# voicemodulator_schm.net
KiCad netlist of a schematic drawn in EAGLE
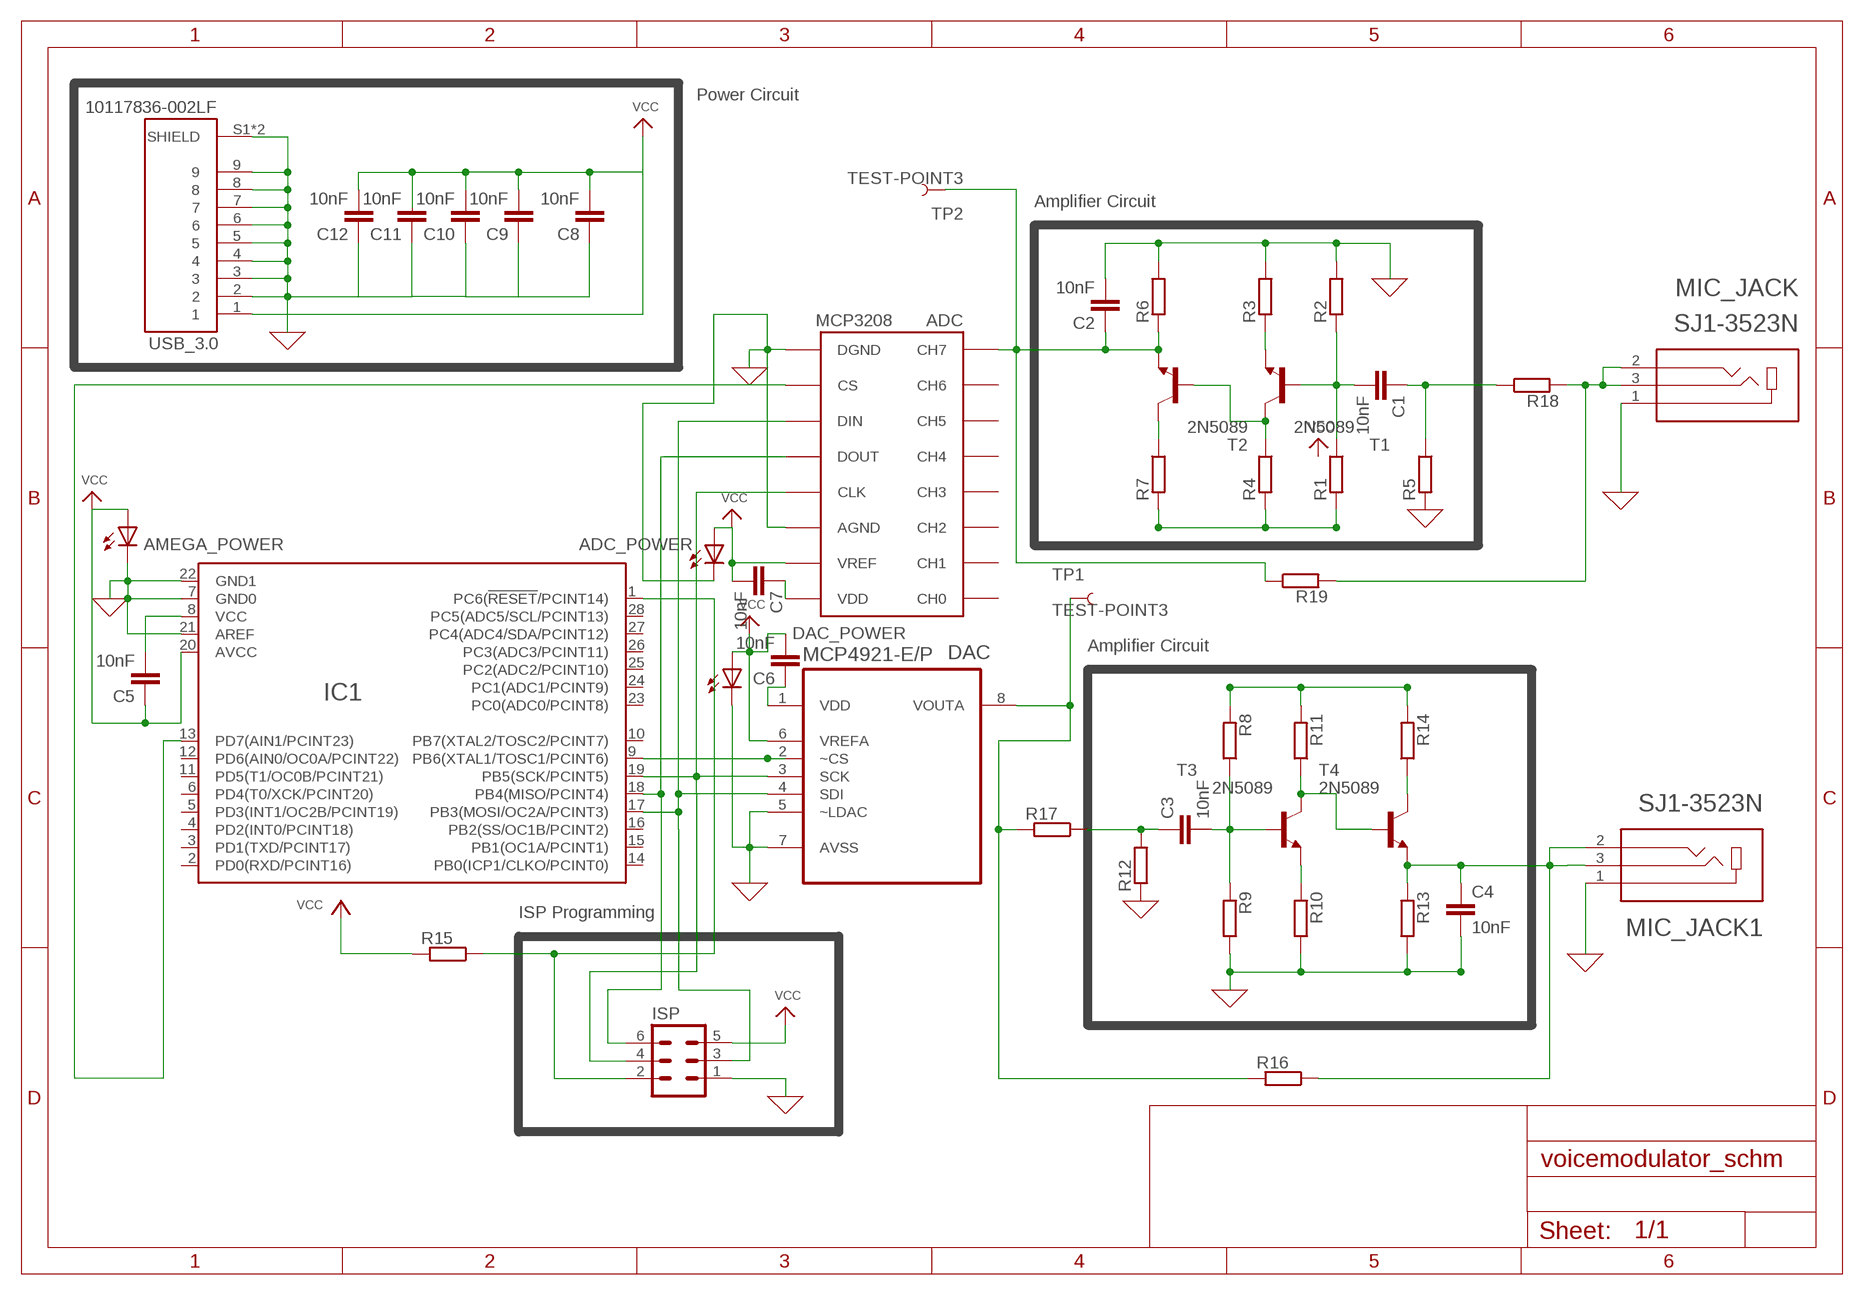
[diagram p0: schematic, sheet 1]

(export (version "E")
  (design (tool "Eeschema 10.0.6"))
  (components
    (comp (ref "ADC")
      (value "MCP3208")
      (footprint "eagle-import:DIL16")
      (libsource (lib "eagle-import") (part "MCP3208"))
    )
    (comp (ref "ADC_POWER")
      (value "LED10MM")
      (footprint "eagle-import:LED10MM")
      (libsource (lib "eagle-import") (part "LED10MM"))
    )
    (comp (ref "AMEGA_POWER")
      (value "LED10MM")
      (footprint "eagle-import:LED10MM")
      (libsource (lib "eagle-import") (part "LED10MM"))
    )
    (comp (ref "C1")
      (value "10nF")
      (footprint "eagle-import:0603")
      (libsource (lib "eagle-import") (part "10NF-0603-50V-10%"))
    )
    (comp (ref "C2")
      (value "10nF")
      (footprint "eagle-import:0603")
      (libsource (lib "eagle-import") (part "10NF-0603-50V-10%"))
    )
    (comp (ref "C3")
      (value "10nF")
      (footprint "eagle-import:0603")
      (libsource (lib "eagle-import") (part "10NF-0603-50V-10%"))
    )
    (comp (ref "C4")
      (value "10nF")
      (footprint "eagle-import:0603")
      (libsource (lib "eagle-import") (part "10NF-0603-50V-10%"))
    )
    (comp (ref "C5")
      (value "10nF")
      (footprint "eagle-import:0603")
      (libsource (lib "eagle-import") (part "10NF-0603-50V-10%"))
    )
    (comp (ref "C6")
      (value "10nF")
      (footprint "eagle-import:0603")
      (libsource (lib "eagle-import") (part "10NF-0603-50V-10%"))
    )
    (comp (ref "C7")
      (value "10nF")
      (footprint "eagle-import:0603")
      (libsource (lib "eagle-import") (part "10NF-0603-50V-10%"))
    )
    (comp (ref "C8")
      (value "10nF")
      (footprint "eagle-import:0603")
      (libsource (lib "eagle-import") (part "10NF-0603-50V-10%"))
    )
    (comp (ref "C9")
      (value "10nF")
      (footprint "eagle-import:0603")
      (libsource (lib "eagle-import") (part "10NF-0603-50V-10%"))
    )
    (comp (ref "C10")
      (value "10nF")
      (footprint "eagle-import:0603")
      (libsource (lib "eagle-import") (part "10NF-0603-50V-10%"))
    )
    (comp (ref "C11")
      (value "10nF")
      (footprint "eagle-import:0603")
      (libsource (lib "eagle-import") (part "10NF-0603-50V-10%"))
    )
    (comp (ref "C12")
      (value "10nF")
      (footprint "eagle-import:0603")
      (libsource (lib "eagle-import") (part "10NF-0603-50V-10%"))
    )
    (comp (ref "DAC")
      (value "MCP4921-E/P")
      (footprint "eagle-import:DIP254P762X432-8")
      (libsource (lib "eagle-import") (part "MCP4921-E/P"))
    )
    (comp (ref "DAC_POWER")
      (value "LED10MM")
      (footprint "eagle-import:LED10MM")
      (libsource (lib "eagle-import") (part "LED10MM"))
    )
    (comp (ref "IC1")
      (value "ATMEGA48/88/168/328-PU(DIP28)PU")
      (footprint "eagle-import:DIL28")
      (libsource (lib "eagle-import") (part "ATMEGA48/88/168/328-PU(DIP28)PU"))
    )
    (comp (ref "ISP")
      (value "MA03-2")
      (footprint "eagle-import:MA03-2")
      (libsource (lib "eagle-import") (part "MA03-2"))
    )
    (comp (ref "MIC_JACK")
      (value "SJ1-3523N")
      (footprint "eagle-import:CUI_SJ1-3523N")
      (fields (field (name "MANUFACTURER") "CUI"))
      (libsource (lib "eagle-import") (part "SJ1-3523N"))
    )
    (comp (ref "MIC_JACK1")
      (value "SJ1-3523N")
      (footprint "eagle-import:CUI_SJ1-3523N")
      (fields (field (name "MANUFACTURER") "CUI"))
      (libsource (lib "eagle-import") (part "SJ1-3523N"))
    )
    (comp (ref "R1")
      (value "SMR-WAV")
      (footprint "eagle-import:SMS-WAV")
      (libsource (lib "eagle-import") (part "SMR-WAV"))
    )
    (comp (ref "R2")
      (value "SMR-WAV")
      (footprint "eagle-import:SMS-WAV")
      (libsource (lib "eagle-import") (part "SMR-WAV"))
    )
    (comp (ref "R3")
      (value "SMR-WAV")
      (footprint "eagle-import:SMS-WAV")
      (libsource (lib "eagle-import") (part "SMR-WAV"))
    )
    (comp (ref "R4")
      (value "SMR-WAV")
      (footprint "eagle-import:SMS-WAV")
      (libsource (lib "eagle-import") (part "SMR-WAV"))
    )
    (comp (ref "R5")
      (value "SMR-WAV")
      (footprint "eagle-import:SMS-WAV")
      (libsource (lib "eagle-import") (part "SMR-WAV"))
    )
    (comp (ref "R6")
      (value "SMR-WAV")
      (footprint "eagle-import:SMS-WAV")
      (libsource (lib "eagle-import") (part "SMR-WAV"))
    )
    (comp (ref "R7")
      (value "SMR-WAV")
      (footprint "eagle-import:SMS-WAV")
      (libsource (lib "eagle-import") (part "SMR-WAV"))
    )
    (comp (ref "R8")
      (value "SMR-WAV")
      (footprint "eagle-import:SMS-WAV")
      (libsource (lib "eagle-import") (part "SMR-WAV"))
    )
    (comp (ref "R9")
      (value "SMR-WAV")
      (footprint "eagle-import:SMS-WAV")
      (libsource (lib "eagle-import") (part "SMR-WAV"))
    )
    (comp (ref "R10")
      (value "SMR-WAV")
      (footprint "eagle-import:SMS-WAV")
      (libsource (lib "eagle-import") (part "SMR-WAV"))
    )
    (comp (ref "R11")
      (value "SMR-WAV")
      (footprint "eagle-import:SMS-WAV")
      (libsource (lib "eagle-import") (part "SMR-WAV"))
    )
    (comp (ref "R12")
      (value "SMR-WAV")
      (footprint "eagle-import:SMS-WAV")
      (libsource (lib "eagle-import") (part "SMR-WAV"))
    )
    (comp (ref "R13")
      (value "SMR-WAV")
      (footprint "eagle-import:SMS-WAV")
      (libsource (lib "eagle-import") (part "SMR-WAV"))
    )
    (comp (ref "R14")
      (value "SMR-WAV")
      (footprint "eagle-import:SMS-WAV")
      (libsource (lib "eagle-import") (part "SMR-WAV"))
    )
    (comp (ref "R15")
      (value "SMR-WAV")
      (footprint "eagle-import:SMS-WAV")
      (libsource (lib "eagle-import") (part "SMR-WAV"))
    )
    (comp (ref "R16")
      (value "SMR-WAV")
      (footprint "eagle-import:SMS-WAV")
      (libsource (lib "eagle-import") (part "SMR-WAV"))
    )
    (comp (ref "R17")
      (value "SMR-WAV")
      (footprint "eagle-import:SMS-WAV")
      (libsource (lib "eagle-import") (part "SMR-WAV"))
    )
    (comp (ref "R18")
      (value "SMR-WAV")
      (footprint "eagle-import:SMS-WAV")
      (libsource (lib "eagle-import") (part "SMR-WAV"))
    )
    (comp (ref "R19")
      (value "SMR-WAV")
      (footprint "eagle-import:SMS-WAV")
      (libsource (lib "eagle-import") (part "SMR-WAV"))
    )
    (comp (ref "T1")
      (value "2N5089")
      (footprint "eagle-import:TO92")
      (libsource (lib "eagle-import") (part "2N5089"))
    )
    (comp (ref "T2")
      (value "2N5089")
      (footprint "eagle-import:TO92")
      (libsource (lib "eagle-import") (part "2N5089"))
    )
    (comp (ref "T3")
      (value "2N5089")
      (footprint "eagle-import:TO92")
      (libsource (lib "eagle-import") (part "2N5089"))
    )
    (comp (ref "T4")
      (value "2N5089")
      (footprint "eagle-import:TO92")
      (libsource (lib "eagle-import") (part "2N5089"))
    )
    (comp (ref "TP1")
      (value "TEST-POINT3")
      (footprint "eagle-import:PAD.03X.03")
      (libsource (lib "eagle-import") (part "TEST-POINT3"))
    )
    (comp (ref "TP2")
      (value "TEST-POINT3")
      (footprint "eagle-import:PAD.03X.03")
      (libsource (lib "eagle-import") (part "TEST-POINT3"))
    )
    (comp (ref "USB_3.0")
      (value "10117836-002LF")
      (footprint "eagle-import:AMPHENOL_10117836-002LF")
      (fields (field (name "MF") "Amphenol FCI"))
      (libsource (lib "eagle-import") (part "10117836-002LF"))
    )
  )
  (nets
    (net (code "1") (name "GND") (class "Default")
      (node (ref "ADC") (pin "AGND") (pinfunction "AGND_AGND") (pintype "power_in"))
      (node (ref "ADC") (pin "DGND") (pinfunction "DGND_DGND") (pintype "power_in"))
      (node (ref "ADC_POWER") (pin "K") (pinfunction "C_K") (pintype "passive"))
      (node (ref "AMEGA_POWER") (pin "K") (pinfunction "C_K") (pintype "passive"))
      (node (ref "C10") (pin "1") (pinfunction "1_1") (pintype "passive"))
      (node (ref "C11") (pin "1") (pinfunction "1_1") (pintype "passive"))
      (node (ref "C12") (pin "1") (pinfunction "1_1") (pintype "passive"))
      (node (ref "C2") (pin "2") (pinfunction "2_2") (pintype "passive"))
      (node (ref "C4") (pin "2") (pinfunction "2_2") (pintype "passive"))
      (node (ref "C8") (pin "1") (pinfunction "1_1") (pintype "passive"))
      (node (ref "C9") (pin "1") (pinfunction "1_1") (pintype "passive"))
      (node (ref "DAC") (pin "5") (pinfunction "~{LDAC}_5") (pintype "input"))
      (node (ref "DAC") (pin "7") (pinfunction "AVSS_7") (pintype "passive"))
      (node (ref "DAC_POWER") (pin "K") (pinfunction "C_K") (pintype "passive"))
      (node (ref "IC1") (pin "21") (pinfunction "AREF_21") (pintype "passive"))
      (node (ref "IC1") (pin "22") (pinfunction "GND1_22") (pintype "power_in"))
      (node (ref "IC1") (pin "7") (pinfunction "GND0_7") (pintype "power_in"))
      (node (ref "ISP") (pin "1") (pinfunction "1_1") (pintype "passive"))
      (node (ref "MIC_JACK") (pin "1") (pinfunction "1_1") (pintype "passive"))
      (node (ref "MIC_JACK1") (pin "1") (pinfunction "1_1") (pintype "passive"))
      (node (ref "R10") (pin "1") (pinfunction "1_1") (pintype "passive"))
      (node (ref "R12") (pin "2") (pinfunction "2_2") (pintype "passive"))
      (node (ref "R13") (pin "1") (pinfunction "1_1") (pintype "passive"))
      (node (ref "R2") (pin "1") (pinfunction "1_1") (pintype "passive"))
      (node (ref "R3") (pin "1") (pinfunction "1_1") (pintype "passive"))
      (node (ref "R5") (pin "2") (pinfunction "2_2") (pintype "passive"))
      (node (ref "R6") (pin "1") (pinfunction "1_1") (pintype "passive"))
      (node (ref "R9") (pin "1") (pinfunction "1_1") (pintype "passive"))
      (node (ref "USB_3.0") (pin "2") (pinfunction "2_2") (pintype "passive"))
      (node (ref "USB_3.0") (pin "3") (pinfunction "3_3") (pintype "passive"))
      (node (ref "USB_3.0") (pin "4") (pinfunction "4_4") (pintype "passive"))
      (node (ref "USB_3.0") (pin "5") (pinfunction "5_5") (pintype "passive"))
      (node (ref "USB_3.0") (pin "6") (pinfunction "6_6") (pintype "passive"))
      (node (ref "USB_3.0") (pin "7") (pinfunction "7_7") (pintype "passive"))
      (node (ref "USB_3.0") (pin "8") (pinfunction "8_8") (pintype "passive"))
      (node (ref "USB_3.0") (pin "9") (pinfunction "9_9") (pintype "passive"))
      (node (ref "USB_3.0") (pin "S1") (pinfunction "SHIELD_S1") (pintype "passive"))
      (node (ref "USB_3.0") (pin "S2") (pinfunction "SHIELD_S2") (pintype "passive"))
    )
    (net (code "2") (name "Net-(ADC-PadVDD)") (class "Default")
      (node (ref "ADC") (pin "VDD") (pinfunction "VDD_VDD") (pintype "power_in"))
      (node (ref "C7") (pin "1") (pinfunction "1_1") (pintype "passive"))
    )
    (net (code "3") (name "Net-(C1-Pad1)") (class "Default")
      (node (ref "C1") (pin "1") (pinfunction "1_1") (pintype "passive"))
      (node (ref "R18") (pin "1") (pinfunction "1_1") (pintype "passive"))
      (node (ref "R5") (pin "1") (pinfunction "1_1") (pintype "passive"))
    )
    (net (code "4") (name "Net-(C3-Pad1)") (class "Default")
      (node (ref "C3") (pin "1") (pinfunction "1_1") (pintype "passive"))
      (node (ref "R12") (pin "1") (pinfunction "1_1") (pintype "passive"))
      (node (ref "R17") (pin "1") (pinfunction "1_1") (pintype "passive"))
    )
    (net (code "5") (name "Net-(DAC-SCK)") (class "Default")
      (node (ref "ADC") (pin "CLK") (pinfunction "CLK_CLK") (pintype "input"))
      (node (ref "DAC") (pin "3") (pinfunction "SCK_3") (pintype "input"))
      (node (ref "IC1") (pin "19") (pinfunction "PB5(SCK/PCINT5)_19") (pintype "bidirectional"))
      (node (ref "ISP") (pin "4") (pinfunction "4_4") (pintype "passive"))
    )
    (net (code "6") (name "Net-(DAC-SDI)") (class "Default")
      (node (ref "ADC") (pin "DIN") (pinfunction "DIN_DIN") (pintype "input"))
      (node (ref "DAC") (pin "4") (pinfunction "SDI_4") (pintype "input"))
      (node (ref "IC1") (pin "17") (pinfunction "PB3(MOSI/OC2A/PCINT3)_17") (pintype "bidirectional"))
      (node (ref "ISP") (pin "3") (pinfunction "3_3") (pintype "passive"))
    )
    (net (code "7") (name "Net-(DAC-VDD)") (class "Default")
      (node (ref "C6") (pin "1") (pinfunction "1_1") (pintype "passive"))
      (node (ref "DAC") (pin "1") (pinfunction "VDD_1") (pintype "power_in"))
    )
    (net (code "8") (name "Net-(DAC-VOUTA)") (class "Default")
      (node (ref "DAC") (pin "8") (pinfunction "VOUTA_8") (pintype "output"))
      (node (ref "R16") (pin "2") (pinfunction "2_2") (pintype "passive"))
      (node (ref "R17") (pin "2") (pinfunction "2_2") (pintype "passive"))
      (node (ref "TP1") (pin "P$1") (pinfunction "1_P$1") (pintype "bidirectional"))
    )
    (net (code "9") (name "Net-(DAC-~{CS})") (class "Default")
      (node (ref "DAC") (pin "2") (pinfunction "~{CS}_2") (pintype "input"))
      (node (ref "IC1") (pin "9") (pinfunction "PB6(XTAL1/TOSC1/PCINT6)_9") (pintype "bidirectional"))
    )
    (net (code "10") (name "Net-(IC1-PB4(MISO{slash}PCINT4))") (class "Default")
      (node (ref "ADC") (pin "DOUT") (pinfunction "DOUT_DOUT") (pintype "output"))
      (node (ref "IC1") (pin "18") (pinfunction "PB4(MISO/PCINT4)_18") (pintype "bidirectional"))
      (node (ref "ISP") (pin "6") (pinfunction "6_6") (pintype "passive"))
    )
    (net (code "11") (name "Net-(IC1-PC6(~{RESET}{slash}PCINT14))") (class "Default")
      (node (ref "IC1") (pin "1") (pinfunction "PC6(~{RESET}/PCINT14)_1") (pintype "bidirectional"))
      (node (ref "ISP") (pin "2") (pinfunction "2_2") (pintype "passive"))
      (node (ref "R15") (pin "1") (pinfunction "1_1") (pintype "passive"))
    )
    (net (code "12") (name "Net-(IC1-PD7(AIN1{slash}PCINT23))") (class "Default")
      (node (ref "ADC") (pin "CS") (pinfunction "CS_CS") (pintype "input"))
      (node (ref "IC1") (pin "13") (pinfunction "PD7(AIN1/PCINT23)_13") (pintype "bidirectional"))
    )
    (net (code "13") (name "Net-(IC1-VCC)") (class "Default")
      (node (ref "C5") (pin "2") (pinfunction "2_2") (pintype "passive"))
      (node (ref "IC1") (pin "8") (pinfunction "VCC_8") (pintype "power_in"))
    )
    (net (code "14") (name "Net-(MIC_JACK-Pad2)") (class "Default")
      (node (ref "MIC_JACK") (pin "2") (pinfunction "2_2") (pintype "passive"))
      (node (ref "MIC_JACK") (pin "3") (pinfunction "3_3") (pintype "passive"))
      (node (ref "R18") (pin "2") (pinfunction "2_2") (pintype "passive"))
      (node (ref "R19") (pin "2") (pinfunction "2_2") (pintype "passive"))
    )
    (net (code "15") (name "Net-(R1-Pad2)") (class "Default")
      (node (ref "R1") (pin "2") (pinfunction "2_2") (pintype "passive"))
      (node (ref "R4") (pin "2") (pinfunction "2_2") (pintype "passive"))
      (node (ref "R7") (pin "2") (pinfunction "2_2") (pintype "passive"))
    )
    (net (code "16") (name "Net-(R11-Pad2)") (class "Default")
      (node (ref "R11") (pin "2") (pinfunction "2_2") (pintype "passive"))
      (node (ref "R14") (pin "2") (pinfunction "2_2") (pintype "passive"))
      (node (ref "R8") (pin "2") (pinfunction "2_2") (pintype "passive"))
    )
    (net (code "17") (name "Net-(T1-B)") (class "Default")
      (node (ref "C1") (pin "2") (pinfunction "2_2") (pintype "passive"))
      (node (ref "R1") (pin "1") (pinfunction "1_1") (pintype "passive"))
      (node (ref "R2") (pin "2") (pinfunction "2_2") (pintype "passive"))
      (node (ref "T1") (pin "2") (pinfunction "B_2") (pintype "passive"))
    )
    (net (code "18") (name "Net-(T1-C)") (class "Default")
      (node (ref "R4") (pin "1") (pinfunction "1_1") (pintype "passive"))
      (node (ref "T1") (pin "1") (pinfunction "C_1") (pintype "passive"))
      (node (ref "T2") (pin "2") (pinfunction "B_2") (pintype "passive"))
    )
    (net (code "19") (name "Net-(T1-E)") (class "Default")
      (node (ref "R3") (pin "2") (pinfunction "2_2") (pintype "passive"))
      (node (ref "T1") (pin "3") (pinfunction "E_3") (pintype "passive"))
    )
    (net (code "20") (name "Net-(T2-C)") (class "Default")
      (node (ref "R7") (pin "1") (pinfunction "1_1") (pintype "passive"))
      (node (ref "T2") (pin "1") (pinfunction "C_1") (pintype "passive"))
    )
    (net (code "21") (name "Net-(T2-E)") (class "Default")
      (node (ref "ADC") (pin "CH7") (pinfunction "CH7_CH7") (pintype "input"))
      (node (ref "C2") (pin "1") (pinfunction "1_1") (pintype "passive"))
      (node (ref "R19") (pin "1") (pinfunction "1_1") (pintype "passive"))
      (node (ref "R6") (pin "2") (pinfunction "2_2") (pintype "passive"))
      (node (ref "T2") (pin "3") (pinfunction "E_3") (pintype "passive"))
      (node (ref "TP2") (pin "P$1") (pinfunction "1_P$1") (pintype "bidirectional"))
    )
    (net (code "22") (name "Net-(T3-B)") (class "Default")
      (node (ref "C3") (pin "2") (pinfunction "2_2") (pintype "passive"))
      (node (ref "R8") (pin "1") (pinfunction "1_1") (pintype "passive"))
      (node (ref "R9") (pin "2") (pinfunction "2_2") (pintype "passive"))
      (node (ref "T3") (pin "2") (pinfunction "B_2") (pintype "passive"))
    )
    (net (code "23") (name "Net-(T3-C)") (class "Default")
      (node (ref "R11") (pin "1") (pinfunction "1_1") (pintype "passive"))
      (node (ref "T3") (pin "1") (pinfunction "C_1") (pintype "passive"))
      (node (ref "T4") (pin "2") (pinfunction "B_2") (pintype "passive"))
    )
    (net (code "24") (name "Net-(T3-E)") (class "Default")
      (node (ref "R10") (pin "2") (pinfunction "2_2") (pintype "passive"))
      (node (ref "T3") (pin "3") (pinfunction "E_3") (pintype "passive"))
    )
    (net (code "25") (name "Net-(T4-C)") (class "Default")
      (node (ref "R14") (pin "1") (pinfunction "1_1") (pintype "passive"))
      (node (ref "T4") (pin "1") (pinfunction "C_1") (pintype "passive"))
    )
    (net (code "26") (name "Net-(T4-E)") (class "Default")
      (node (ref "C4") (pin "1") (pinfunction "1_1") (pintype "passive"))
      (node (ref "MIC_JACK1") (pin "2") (pinfunction "2_2") (pintype "passive"))
      (node (ref "MIC_JACK1") (pin "3") (pinfunction "3_3") (pintype "passive"))
      (node (ref "R13") (pin "2") (pinfunction "2_2") (pintype "passive"))
      (node (ref "R16") (pin "1") (pinfunction "1_1") (pintype "passive"))
      (node (ref "T4") (pin "3") (pinfunction "E_3") (pintype "passive"))
    )
    (net (code "27") (name "VCC") (class "Default")
      (node (ref "ADC") (pin "VREF") (pinfunction "VREF_VREF") (pintype "input"))
      (node (ref "ADC_POWER") (pin "A") (pinfunction "A_A") (pintype "passive"))
      (node (ref "AMEGA_POWER") (pin "A") (pinfunction "A_A") (pintype "passive"))
      (node (ref "C10") (pin "2") (pinfunction "2_2") (pintype "passive"))
      (node (ref "C12") (pin "2") (pinfunction "2_2") (pintype "passive"))
      (node (ref "C5") (pin "1") (pinfunction "1_1") (pintype "passive"))
      (node (ref "C6") (pin "2") (pinfunction "2_2") (pintype "passive"))
      (node (ref "C7") (pin "2") (pinfunction "2_2") (pintype "passive"))
      (node (ref "C8") (pin "2") (pinfunction "2_2") (pintype "passive"))
      (node (ref "C9") (pin "2") (pinfunction "2_2") (pintype "passive"))
      (node (ref "DAC") (pin "6") (pinfunction "VREFA_6") (pintype "input"))
      (node (ref "DAC_POWER") (pin "A") (pinfunction "A_A") (pintype "passive"))
      (node (ref "IC1") (pin "20") (pinfunction "AVCC_20") (pintype "power_in"))
      (node (ref "ISP") (pin "5") (pinfunction "5_5") (pintype "passive"))
      (node (ref "R15") (pin "2") (pinfunction "2_2") (pintype "passive"))
      (node (ref "USB_3.0") (pin "1") (pinfunction "1_1") (pintype "passive"))
    )
    (net (code "28") (name "unconnected-(ADC-PadCH0)") (class "Default")
      (node (ref "ADC") (pin "CH0") (pinfunction "CH0_CH0") (pintype "input"))
    )
    (net (code "29") (name "unconnected-(ADC-PadCH1)") (class "Default")
      (node (ref "ADC") (pin "CH1") (pinfunction "CH1_CH1") (pintype "input"))
    )
    (net (code "30") (name "unconnected-(ADC-PadCH2)") (class "Default")
      (node (ref "ADC") (pin "CH2") (pinfunction "CH2_CH2") (pintype "input"))
    )
    (net (code "31") (name "unconnected-(ADC-PadCH3)") (class "Default")
      (node (ref "ADC") (pin "CH3") (pinfunction "CH3_CH3") (pintype "input"))
    )
    (net (code "32") (name "unconnected-(ADC-PadCH4)") (class "Default")
      (node (ref "ADC") (pin "CH4") (pinfunction "CH4_CH4") (pintype "input"))
    )
    (net (code "33") (name "unconnected-(ADC-PadCH5)") (class "Default")
      (node (ref "ADC") (pin "CH5") (pinfunction "CH5_CH5") (pintype "input"))
    )
    (net (code "34") (name "unconnected-(ADC-PadCH6)") (class "Default")
      (node (ref "ADC") (pin "CH6") (pinfunction "CH6_CH6") (pintype "input"))
    )
    (net (code "35") (name "unconnected-(C11-Pad2)") (class "Default")
      (node (ref "C11") (pin "2") (pinfunction "2_2") (pintype "passive"))
    )
    (net (code "36") (name "unconnected-(IC1-PB0(ICP1{slash}CLKO{slash}PCINT0)-Pad14)") (class "Default")
      (node (ref "IC1") (pin "14") (pinfunction "PB0(ICP1/CLKO/PCINT0)_14") (pintype "bidirectional"))
    )
    (net (code "37") (name "unconnected-(IC1-PB1(OC1A{slash}PCINT1)-Pad15)") (class "Default")
      (node (ref "IC1") (pin "15") (pinfunction "PB1(OC1A/PCINT1)_15") (pintype "bidirectional"))
    )
    (net (code "38") (name "unconnected-(IC1-PB2(SS{slash}OC1B{slash}PCINT2)-Pad16)") (class "Default")
      (node (ref "IC1") (pin "16") (pinfunction "PB2(SS/OC1B/PCINT2)_16") (pintype "bidirectional"))
    )
    (net (code "39") (name "unconnected-(IC1-PB7(XTAL2{slash}TOSC2{slash}PCINT7)-Pad10)") (class "Default")
      (node (ref "IC1") (pin "10") (pinfunction "PB7(XTAL2/TOSC2/PCINT7)_10") (pintype "bidirectional"))
    )
    (net (code "40") (name "unconnected-(IC1-PC0(ADC0{slash}PCINT8)-Pad23)") (class "Default")
      (node (ref "IC1") (pin "23") (pinfunction "PC0(ADC0/PCINT8)_23") (pintype "bidirectional"))
    )
    (net (code "41") (name "unconnected-(IC1-PC1(ADC1{slash}PCINT9)-Pad24)") (class "Default")
      (node (ref "IC1") (pin "24") (pinfunction "PC1(ADC1/PCINT9)_24") (pintype "bidirectional"))
    )
    (net (code "42") (name "unconnected-(IC1-PC2(ADC2{slash}PCINT10)-Pad25)") (class "Default")
      (node (ref "IC1") (pin "25") (pinfunction "PC2(ADC2/PCINT10)_25") (pintype "bidirectional"))
    )
    (net (code "43") (name "unconnected-(IC1-PC3(ADC3{slash}PCINT11)-Pad26)") (class "Default")
      (node (ref "IC1") (pin "26") (pinfunction "PC3(ADC3/PCINT11)_26") (pintype "bidirectional"))
    )
    (net (code "44") (name "unconnected-(IC1-PC4(ADC4{slash}SDA{slash}PCINT12)-Pad27)") (class "Default")
      (node (ref "IC1") (pin "27") (pinfunction "PC4(ADC4/SDA/PCINT12)_27") (pintype "bidirectional"))
    )
    (net (code "45") (name "unconnected-(IC1-PC5(ADC5{slash}SCL{slash}PCINT13)-Pad28)") (class "Default")
      (node (ref "IC1") (pin "28") (pinfunction "PC5(ADC5/SCL/PCINT13)_28") (pintype "bidirectional"))
    )
    (net (code "46") (name "unconnected-(IC1-PD0(RXD{slash}PCINT16)-Pad2)") (class "Default")
      (node (ref "IC1") (pin "2") (pinfunction "PD0(RXD/PCINT16)_2") (pintype "bidirectional"))
    )
    (net (code "47") (name "unconnected-(IC1-PD1(TXD{slash}PCINT17)-Pad3)") (class "Default")
      (node (ref "IC1") (pin "3") (pinfunction "PD1(TXD/PCINT17)_3") (pintype "bidirectional"))
    )
    (net (code "48") (name "unconnected-(IC1-PD2(INT0{slash}PCINT18)-Pad4)") (class "Default")
      (node (ref "IC1") (pin "4") (pinfunction "PD2(INT0/PCINT18)_4") (pintype "bidirectional"))
    )
    (net (code "49") (name "unconnected-(IC1-PD3(INT1{slash}OC2B{slash}PCINT19)-Pad5)") (class "Default")
      (node (ref "IC1") (pin "5") (pinfunction "PD3(INT1/OC2B/PCINT19)_5") (pintype "bidirectional"))
    )
    (net (code "50") (name "unconnected-(IC1-PD4(T0{slash}XCK{slash}PCINT20)-Pad6)") (class "Default")
      (node (ref "IC1") (pin "6") (pinfunction "PD4(T0/XCK/PCINT20)_6") (pintype "bidirectional"))
    )
    (net (code "51") (name "unconnected-(IC1-PD5(T1{slash}OC0B{slash}PCINT21)-Pad11)") (class "Default")
      (node (ref "IC1") (pin "11") (pinfunction "PD5(T1/OC0B/PCINT21)_11") (pintype "bidirectional"))
    )
    (net (code "52") (name "unconnected-(IC1-PD6(AIN0{slash}OC0A{slash}PCINT22)-Pad12)") (class "Default")
      (node (ref "IC1") (pin "12") (pinfunction "PD6(AIN0/OC0A/PCINT22)_12") (pintype "bidirectional"))
    )
  )
)
